# Low-Frequency-LC-Oscillator.net
KiCad netlist of a schematic drawn in EAGLE
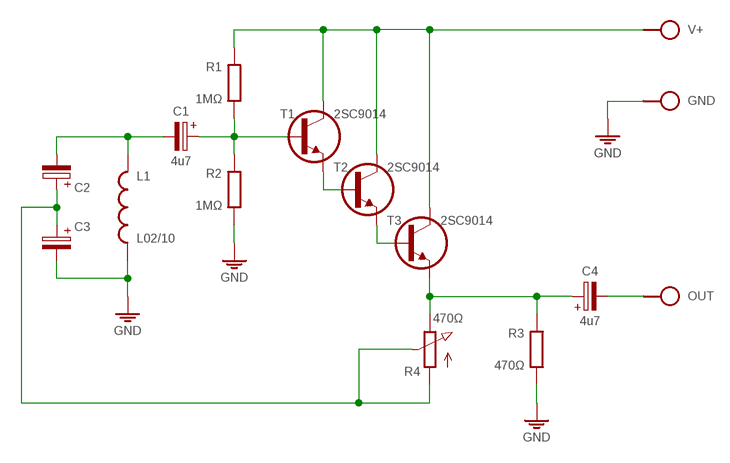
[diagram p0: schematic, sheet 1]

(export (version "E")
  (design (tool "Eeschema 10.0.6"))
  (components
    (comp (ref "C1")
      (value "4u7")
      (footprint "eagle-import:E2,5-3")
      (libsource (lib "eagle-import") (part "CPOLE2,5-3"))
    )
    (comp (ref "C2")
      (value "CPOLE2.5-5")
      (footprint "eagle-import:E2,5-5")
      (libsource (lib "eagle-import") (part "CPOLE2.5-5"))
    )
    (comp (ref "C3")
      (value "CPOLE2.5-5")
      (footprint "eagle-import:E2,5-5")
      (libsource (lib "eagle-import") (part "CPOLE2.5-5"))
    )
    (comp (ref "C4")
      (value "4u7")
      (footprint "eagle-import:E2,5-3")
      (libsource (lib "eagle-import") (part "CPOLE2,5-3"))
    )
    (comp (ref "GND")
      (value "SPAD")
      (footprint "eagle-import:SPAD")
      (libsource (lib "eagle-import") (part "SPAD"))
    )
    (comp (ref "L1")
      (value "L02/10")
      (footprint "eagle-import:L-03_10V")
      (libsource (lib "eagle-import") (part "L02/10"))
    )
    (comp (ref "OUT")
      (value "SPAD")
      (footprint "eagle-import:SPAD")
      (libsource (lib "eagle-import") (part "SPAD"))
    )
    (comp (ref "R1")
      (value "1MΩ")
      (footprint "eagle-import:0204_10")
      (libsource (lib "eagle-import") (part "R0204/10"))
    )
    (comp (ref "R2")
      (value "1MΩ")
      (footprint "eagle-import:0204_10")
      (libsource (lib "eagle-import") (part "R0204/10"))
    )
    (comp (ref "R3")
      (value "470Ω")
      (footprint "eagle-import:0204_10")
      (libsource (lib "eagle-import") (part "R0204/10"))
    )
    (comp (ref "R4")
      (value "470Ω")
      (footprint "eagle-import:POT")
      (libsource (lib "eagle-import") (part "POT"))
    )
    (comp (ref "T1")
      (value "2SC9014")
      (footprint "eagle-import:TO92-EBC")
      (libsource (lib "eagle-import") (part "2SC9014"))
    )
    (comp (ref "T2")
      (value "2SC9014")
      (footprint "eagle-import:TO92-EBC")
      (libsource (lib "eagle-import") (part "2SC9014"))
    )
    (comp (ref "T3")
      (value "2SC9014")
      (footprint "eagle-import:TO92-EBC")
      (libsource (lib "eagle-import") (part "2SC9014"))
    )
    (comp (ref "V+")
      (value "SPAD")
      (footprint "eagle-import:SPAD")
      (libsource (lib "eagle-import") (part "SPAD"))
    )
  )
  (nets
    (net (code "1") (name "GND") (class "Default")
      (node (ref "C3") (pin "-") (pinfunction "-_-") (pintype "passive"))
      (node (ref "GND") (pin "1") (pinfunction "P$1_1") (pintype "bidirectional"))
      (node (ref "L1") (pin "2") (pinfunction "2_2") (pintype "passive"))
      (node (ref "R2") (pin "1") (pinfunction "1_1") (pintype "passive"))
      (node (ref "R3") (pin "1") (pinfunction "1_1") (pintype "passive"))
    )
    (net (code "2") (name "Net-(C1-Pad+)") (class "Default")
      (node (ref "C1") (pin "+") (pinfunction "+_+") (pintype "passive"))
      (node (ref "R1") (pin "1") (pinfunction "1_1") (pintype "passive"))
      (node (ref "R2") (pin "2") (pinfunction "2_2") (pintype "passive"))
      (node (ref "T1") (pin "B") (pinfunction "B_B") (pintype "passive"))
    )
    (net (code "3") (name "Net-(C1-Pad-)") (class "Default")
      (node (ref "C1") (pin "-") (pinfunction "-_-") (pintype "passive"))
      (node (ref "C2") (pin "-") (pinfunction "-_-") (pintype "passive"))
      (node (ref "L1") (pin "1") (pinfunction "1_1") (pintype "passive"))
    )
    (net (code "4") (name "Net-(OUT-P$1)") (class "Default")
      (node (ref "C4") (pin "-") (pinfunction "-_-") (pintype "passive"))
      (node (ref "OUT") (pin "1") (pinfunction "P$1_1") (pintype "bidirectional"))
    )
    (net (code "5") (name "Net-(R4-A)") (class "Default")
      (node (ref "C2") (pin "+") (pinfunction "+_+") (pintype "passive"))
      (node (ref "C3") (pin "+") (pinfunction "+_+") (pintype "passive"))
      (node (ref "R4") (pin "1") (pinfunction "A_1") (pintype "passive"))
      (node (ref "R4") (pin "2") (pinfunction "S_2") (pintype "passive"))
    )
    (net (code "6") (name "Net-(R4-E)") (class "Default")
      (node (ref "C4") (pin "+") (pinfunction "+_+") (pintype "passive"))
      (node (ref "R3") (pin "2") (pinfunction "2_2") (pintype "passive"))
      (node (ref "R4") (pin "3") (pinfunction "E_3") (pintype "passive"))
      (node (ref "T3") (pin "E") (pinfunction "E_E") (pintype "passive"))
    )
    (net (code "7") (name "Net-(T1-PadE)") (class "Default")
      (node (ref "T1") (pin "E") (pinfunction "E_E") (pintype "passive"))
      (node (ref "T2") (pin "B") (pinfunction "B_B") (pintype "passive"))
    )
    (net (code "8") (name "Net-(T2-PadE)") (class "Default")
      (node (ref "T2") (pin "E") (pinfunction "E_E") (pintype "passive"))
      (node (ref "T3") (pin "B") (pinfunction "B_B") (pintype "passive"))
    )
    (net (code "9") (name "Net-(V+-P$1)") (class "Default")
      (node (ref "R1") (pin "2") (pinfunction "2_2") (pintype "passive"))
      (node (ref "T1") (pin "C") (pinfunction "C_C") (pintype "passive"))
      (node (ref "T2") (pin "C") (pinfunction "C_C") (pintype "passive"))
      (node (ref "T3") (pin "C") (pinfunction "C_C") (pintype "passive"))
      (node (ref "V+") (pin "1") (pinfunction "P$1_1") (pintype "bidirectional"))
    )
  )
)
